# vakuum2.net
KiCad netlist of a schematic drawn in EAGLE
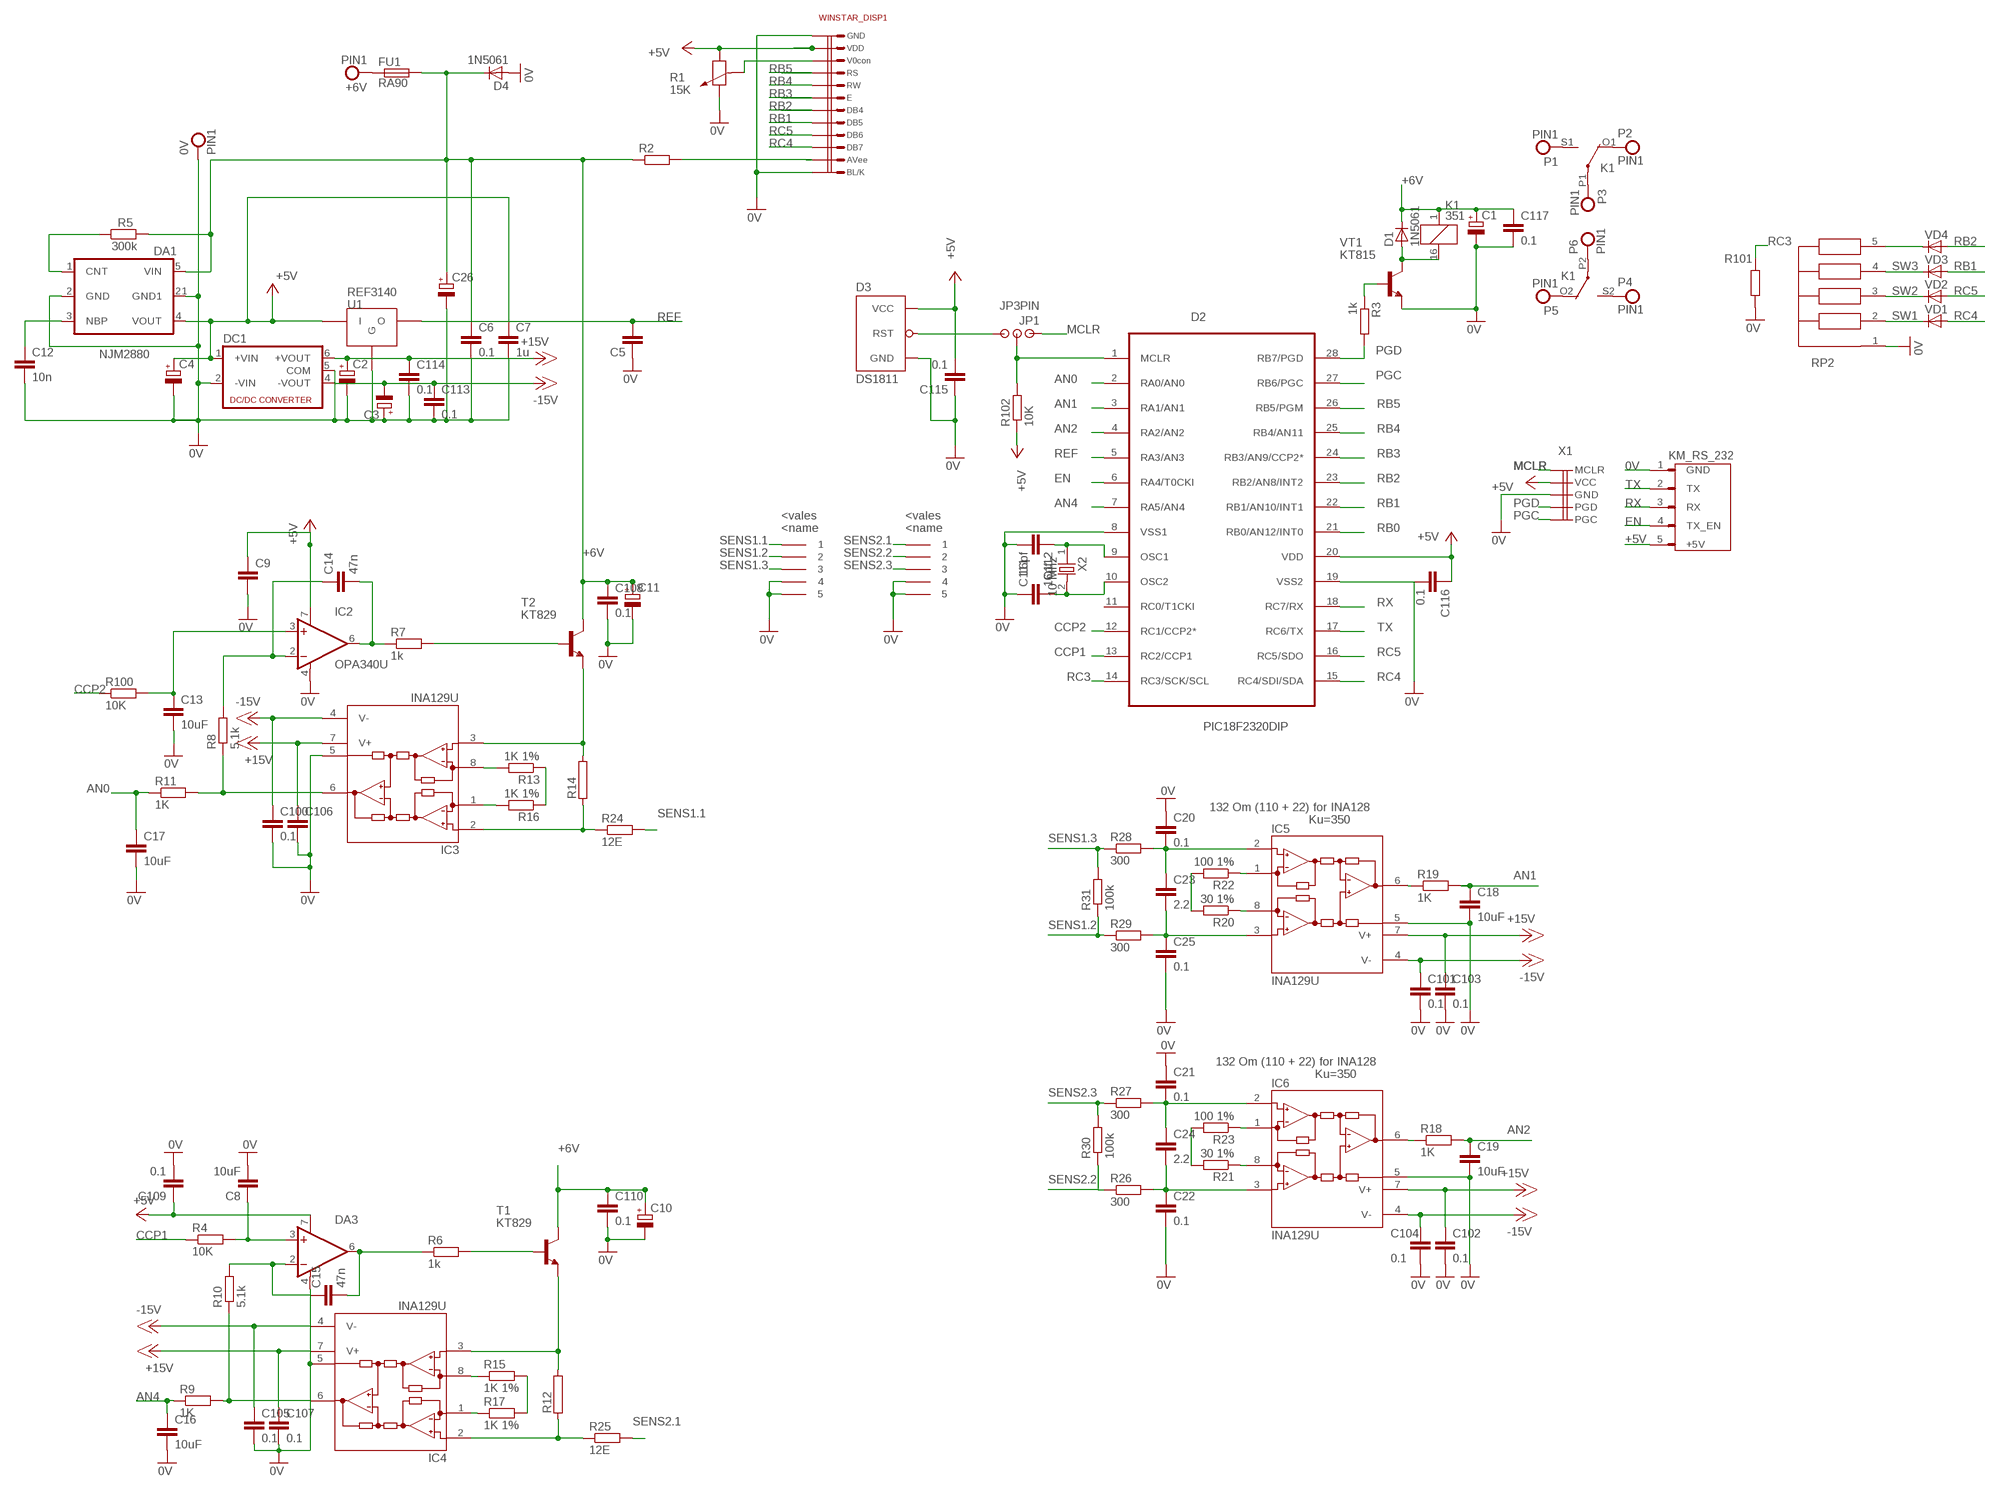
[diagram p0: schematic, sheet 1]

(export (version "E")
  (design (tool "Eeschema 10.0.6"))
  (components
    (comp (ref "+6V")
      (value "PIN1")
      (footprint "eagle-import:PIN1")
      (libsource (lib "eagle-import") (part "PIN1"))
    )
    (comp (ref "0V")
      (value "PIN1")
      (footprint "eagle-import:PIN1")
      (libsource (lib "eagle-import") (part "PIN1"))
    )
    (comp (ref "C1")
      (value "C100MFX25V")
      (footprint "eagle-import:C100MILX6X12")
      (libsource (lib "eagle-import") (part "C100MFX25V"))
    )
    (comp (ref "C2")
      (value "C100MFX25V")
      (footprint "eagle-import:C100MILX6X12")
      (libsource (lib "eagle-import") (part "C100MFX25V"))
    )
    (comp (ref "C3")
      (value "C100MFX25V")
      (footprint "eagle-import:C100MILX6X12")
      (libsource (lib "eagle-import") (part "C100MFX25V"))
    )
    (comp (ref "C4")
      (value "C100MFX25V")
      (footprint "eagle-import:C100MILX6X12")
      (libsource (lib "eagle-import") (part "C100MFX25V"))
    )
    (comp (ref "C5")
      (value "C0805")
      (footprint "eagle-import:C0805D")
      (libsource (lib "eagle-import") (part "C0805"))
    )
    (comp (ref "C6")
      (value "0.1")
      (footprint "eagle-import:C0805D")
      (libsource (lib "eagle-import") (part "C0805"))
    )
    (comp (ref "C7")
      (value "1u")
      (footprint "eagle-import:C0805D")
      (libsource (lib "eagle-import") (part "C0805"))
    )
    (comp (ref "C8")
      (value "10uF")
      (footprint "eagle-import:C0805D")
      (libsource (lib "eagle-import") (part "C0805"))
    )
    (comp (ref "C9")
      (value "C0805")
      (footprint "eagle-import:C0805D")
      (libsource (lib "eagle-import") (part "C0805"))
    )
    (comp (ref "C10")
      (value "C100MFX25V")
      (footprint "eagle-import:C100MILX6X12")
      (libsource (lib "eagle-import") (part "C100MFX25V"))
    )
    (comp (ref "C11")
      (value "C100MFX25V")
      (footprint "eagle-import:C100MILX6X12")
      (libsource (lib "eagle-import") (part "C100MFX25V"))
    )
    (comp (ref "C12")
      (value "10n")
      (footprint "eagle-import:C0805D")
      (libsource (lib "eagle-import") (part "C0805"))
    )
    (comp (ref "C13")
      (value "10uF")
      (footprint "eagle-import:C0805D")
      (libsource (lib "eagle-import") (part "C0805"))
    )
    (comp (ref "C14")
      (value "47n")
      (footprint "eagle-import:C0805D")
      (libsource (lib "eagle-import") (part "C0805"))
    )
    (comp (ref "C15")
      (value "47n")
      (footprint "eagle-import:C0805D")
      (libsource (lib "eagle-import") (part "C0805"))
    )
    (comp (ref "C16")
      (value "10uF")
      (footprint "eagle-import:C0805D")
      (libsource (lib "eagle-import") (part "C0805"))
    )
    (comp (ref "C17")
      (value "10uF")
      (footprint "eagle-import:C0805D")
      (libsource (lib "eagle-import") (part "C0805"))
    )
    (comp (ref "C18")
      (value "10uF")
      (footprint "eagle-import:C0805D")
      (libsource (lib "eagle-import") (part "C0805"))
    )
    (comp (ref "C19")
      (value "10uF")
      (footprint "eagle-import:C0805D")
      (libsource (lib "eagle-import") (part "C0805"))
    )
    (comp (ref "C20")
      (value "0.1")
      (footprint "eagle-import:C0805D")
      (libsource (lib "eagle-import") (part "C0805"))
    )
    (comp (ref "C21")
      (value "0.1")
      (footprint "eagle-import:C0805D")
      (libsource (lib "eagle-import") (part "C0805"))
    )
    (comp (ref "C22")
      (value "0.1")
      (footprint "eagle-import:C0805D")
      (libsource (lib "eagle-import") (part "C0805"))
    )
    (comp (ref "C23")
      (value "2.2")
      (footprint "eagle-import:C0805D")
      (libsource (lib "eagle-import") (part "C0805"))
    )
    (comp (ref "C24")
      (value "2.2")
      (footprint "eagle-import:C0805D")
      (libsource (lib "eagle-import") (part "C0805"))
    )
    (comp (ref "C25")
      (value "0.1")
      (footprint "eagle-import:C0805D")
      (libsource (lib "eagle-import") (part "C0805"))
    )
    (comp (ref "C26")
      (value "C100MFX25V")
      (footprint "eagle-import:C100MILX6X12")
      (libsource (lib "eagle-import") (part "C100MFX25V"))
    )
    (comp (ref "C100")
      (value "0.1")
      (footprint "eagle-import:C0805D")
      (libsource (lib "eagle-import") (part "C0805"))
    )
    (comp (ref "C101")
      (value "0.1")
      (footprint "eagle-import:C0805D")
      (libsource (lib "eagle-import") (part "C0805"))
    )
    (comp (ref "C102")
      (value "0.1")
      (footprint "eagle-import:C0805D")
      (libsource (lib "eagle-import") (part "C0805"))
    )
    (comp (ref "C103")
      (value "0.1")
      (footprint "eagle-import:C0805D")
      (libsource (lib "eagle-import") (part "C0805"))
    )
    (comp (ref "C104")
      (value "0.1")
      (footprint "eagle-import:C0805D")
      (libsource (lib "eagle-import") (part "C0805"))
    )
    (comp (ref "C105")
      (value "0.1")
      (footprint "eagle-import:C0805D")
      (libsource (lib "eagle-import") (part "C0805"))
    )
    (comp (ref "C106")
      (value "C0805")
      (footprint "eagle-import:C0805D")
      (libsource (lib "eagle-import") (part "C0805"))
    )
    (comp (ref "C107")
      (value "0.1")
      (footprint "eagle-import:C0805D")
      (libsource (lib "eagle-import") (part "C0805"))
    )
    (comp (ref "C108")
      (value "0.1")
      (footprint "eagle-import:C0805D")
      (libsource (lib "eagle-import") (part "C0805"))
    )
    (comp (ref "C109")
      (value "0.1")
      (footprint "eagle-import:C0805D")
      (libsource (lib "eagle-import") (part "C0805"))
    )
    (comp (ref "C110")
      (value "0.1")
      (footprint "eagle-import:C0805D")
      (libsource (lib "eagle-import") (part "C0805"))
    )
    (comp (ref "C111")
      (value "16pf")
      (footprint "eagle-import:C0805D")
      (libsource (lib "eagle-import") (part "C0805"))
    )
    (comp (ref "C112")
      (value "16pf")
      (footprint "eagle-import:C0805D")
      (libsource (lib "eagle-import") (part "C0805"))
    )
    (comp (ref "C113")
      (value "0.1")
      (footprint "eagle-import:C0805D")
      (libsource (lib "eagle-import") (part "C0805"))
    )
    (comp (ref "C114")
      (value "0.1")
      (footprint "eagle-import:C0805D")
      (libsource (lib "eagle-import") (part "C0805"))
    )
    (comp (ref "C115")
      (value "0.1")
      (footprint "eagle-import:C0805D")
      (libsource (lib "eagle-import") (part "C0805"))
    )
    (comp (ref "C116")
      (value "0.1")
      (footprint "eagle-import:C0805D")
      (libsource (lib "eagle-import") (part "C0805"))
    )
    (comp (ref "C117")
      (value "0.1")
      (footprint "eagle-import:C0805D")
      (libsource (lib "eagle-import") (part "C0805"))
    )
    (comp (ref "D1")
      (value "1N5061")
      (footprint "eagle-import:DO41-10")
      (libsource (lib "eagle-import") (part "1N5061"))
    )
    (comp (ref "D2")
      (value "PIC18F2320DIP")
      (footprint "eagle-import:DIL28-3")
      (libsource (lib "eagle-import") (part "PIC18F2320DIP"))
    )
    (comp (ref "D3")
      (value "DS1811")
      (footprint "eagle-import:TO92-60")
      (libsource (lib "eagle-import") (part "DS1811"))
    )
    (comp (ref "D4")
      (value "1N5061")
      (footprint "eagle-import:DO41-10")
      (libsource (lib "eagle-import") (part "1N5061"))
    )
    (comp (ref "DA1")
      (value "NJM2880")
      (footprint "eagle-import:SOT89-5")
      (libsource (lib "eagle-import") (part "NJM2880"))
    )
    (comp (ref "DA3")
      (value "OPA340U")
      (footprint "eagle-import:SO08")
      (fields (field (name "MPN") "OPA340UA"))
      (libsource (lib "eagle-import") (part "OPA340U"))
    )
    (comp (ref "DC1")
      (value "NMA")
      (footprint "eagle-import:NMA")
      (fields (field (name "MF") "C & D TECHNOLOGIES, INC") (field (name "MPN") "NMA0515SC"))
      (libsource (lib "eagle-import") (part "NMA"))
    )
    (comp (ref "FU1")
      (value "RA90")
      (footprint "eagle-import:RA90")
      (libsource (lib "eagle-import") (part "RA90"))
    )
    (comp (ref "IC2")
      (value "OPA340U")
      (footprint "eagle-import:SO08")
      (fields (field (name "MPN") "OPA340UA"))
      (libsource (lib "eagle-import") (part "OPA340U"))
    )
    (comp (ref "IC3")
      (value "INA129U")
      (footprint "eagle-import:SO08")
      (fields (field (name "MF") "TEXAS INSTRUMENTS"))
      (libsource (lib "eagle-import") (part "INA129U"))
    )
    (comp (ref "IC4")
      (value "INA129U")
      (footprint "eagle-import:SO08")
      (fields (field (name "MF") "TEXAS INSTRUMENTS"))
      (libsource (lib "eagle-import") (part "INA129U"))
    )
    (comp (ref "IC5")
      (value "INA129U")
      (footprint "eagle-import:SO08")
      (fields (field (name "MF") "TEXAS INSTRUMENTS"))
      (libsource (lib "eagle-import") (part "INA129U"))
    )
    (comp (ref "IC6")
      (value "INA129U")
      (footprint "eagle-import:SO08")
      (fields (field (name "MF") "TEXAS INSTRUMENTS"))
      (libsource (lib "eagle-import") (part "INA129U"))
    )
    (comp (ref "JP1")
      (value "JP3PIN")
      (footprint "eagle-import:PLC-3PIN")
      (libsource (lib "eagle-import") (part "JP3PIN"))
    )
    (comp (ref "K1")
      (value "351")
      (footprint "eagle-import:351")
      (libsource (lib "eagle-import") (part "351"))
    )
    (comp (ref "P1")
      (value "PIN1")
      (footprint "eagle-import:PIN1")
      (libsource (lib "eagle-import") (part "PIN1"))
    )
    (comp (ref "P2")
      (value "PIN1")
      (footprint "eagle-import:PIN1")
      (libsource (lib "eagle-import") (part "PIN1"))
    )
    (comp (ref "P3")
      (value "PIN1")
      (footprint "eagle-import:PIN1")
      (libsource (lib "eagle-import") (part "PIN1"))
    )
    (comp (ref "P4")
      (value "PIN1")
      (footprint "eagle-import:PIN1")
      (libsource (lib "eagle-import") (part "PIN1"))
    )
    (comp (ref "P5")
      (value "PIN1")
      (footprint "eagle-import:PIN1")
      (libsource (lib "eagle-import") (part "PIN1"))
    )
    (comp (ref "P6")
      (value "PIN1")
      (footprint "eagle-import:PIN1")
      (libsource (lib "eagle-import") (part "PIN1"))
    )
    (comp (ref "R1")
      (value "15K")
      (footprint "eagle-import:RTRIM3329H")
      (libsource (lib "eagle-import") (part "RTRIM3329H"))
    )
    (comp (ref "R2")
      (value "MLT025\"")
      (footprint "eagle-import:0207_10")
      (libsource (lib "eagle-import") (part "MLT025{dblquote}"))
    )
    (comp (ref "R3")
      (value "1k")
      (footprint "eagle-import:0207_10")
      (libsource (lib "eagle-import") (part "MLT025{dblquote}"))
    )
    (comp (ref "R4")
      (value "10K")
      (footprint "eagle-import:R0805D")
      (libsource (lib "eagle-import") (part "R0805"))
    )
    (comp (ref "R5")
      (value "300k")
      (footprint "eagle-import:R0805D")
      (libsource (lib "eagle-import") (part "R0805"))
    )
    (comp (ref "R6")
      (value "1k")
      (footprint "eagle-import:0207_10")
      (libsource (lib "eagle-import") (part "MLT025{dblquote}"))
    )
    (comp (ref "R7")
      (value "1k")
      (footprint "eagle-import:R0805D")
      (libsource (lib "eagle-import") (part "R0805"))
    )
    (comp (ref "R8")
      (value "5.1k")
      (footprint "eagle-import:R0805D")
      (libsource (lib "eagle-import") (part "R0805"))
    )
    (comp (ref "R9")
      (value "1K")
      (footprint "eagle-import:R0805D")
      (libsource (lib "eagle-import") (part "R0805"))
    )
    (comp (ref "R10")
      (value "5.1k")
      (footprint "eagle-import:R0805D")
      (libsource (lib "eagle-import") (part "R0805"))
    )
    (comp (ref "R11")
      (value "1K")
      (footprint "eagle-import:R0805D")
      (libsource (lib "eagle-import") (part "R0805"))
    )
    (comp (ref "R12")
      (value "RHPS932")
      (footprint "eagle-import:HPS932")
      (libsource (lib "eagle-import") (part "RHPS932"))
    )
    (comp (ref "R13")
      (value "1K 1%")
      (footprint "eagle-import:R0805D")
      (libsource (lib "eagle-import") (part "R0805"))
    )
    (comp (ref "R14")
      (value "RHPS932")
      (footprint "eagle-import:HPS932")
      (libsource (lib "eagle-import") (part "RHPS932"))
    )
    (comp (ref "R15")
      (value "1K 1%")
      (footprint "eagle-import:R0805D")
      (libsource (lib "eagle-import") (part "R0805"))
    )
    (comp (ref "R16")
      (value "1K 1%")
      (footprint "eagle-import:R0805D")
      (libsource (lib "eagle-import") (part "R0805"))
    )
    (comp (ref "R17")
      (value "1K 1%")
      (footprint "eagle-import:R0805D")
      (libsource (lib "eagle-import") (part "R0805"))
    )
    (comp (ref "R18")
      (value "1K")
      (footprint "eagle-import:R0805D")
      (libsource (lib "eagle-import") (part "R0805"))
    )
    (comp (ref "R19")
      (value "1K")
      (footprint "eagle-import:R0805D")
      (libsource (lib "eagle-import") (part "R0805"))
    )
    (comp (ref "R20")
      (value "30 1%")
      (footprint "eagle-import:R0805D")
      (libsource (lib "eagle-import") (part "R0805"))
    )
    (comp (ref "R21")
      (value "30 1%")
      (footprint "eagle-import:R0805D")
      (libsource (lib "eagle-import") (part "R0805"))
    )
    (comp (ref "R22")
      (value "100 1%")
      (footprint "eagle-import:R0805D")
      (libsource (lib "eagle-import") (part "R0805"))
    )
    (comp (ref "R23")
      (value "100 1%")
      (footprint "eagle-import:R0805D")
      (libsource (lib "eagle-import") (part "R0805"))
    )
    (comp (ref "R24")
      (value "12E")
      (footprint "eagle-import:0207_10")
      (libsource (lib "eagle-import") (part "MLT025{dblquote}"))
    )
    (comp (ref "R25")
      (value "12E")
      (footprint "eagle-import:0207_10")
      (libsource (lib "eagle-import") (part "MLT025{dblquote}"))
    )
    (comp (ref "R26")
      (value "300")
      (footprint "eagle-import:R0805D")
      (libsource (lib "eagle-import") (part "R0805"))
    )
    (comp (ref "R27")
      (value "300")
      (footprint "eagle-import:R0805D")
      (libsource (lib "eagle-import") (part "R0805"))
    )
    (comp (ref "R28")
      (value "300")
      (footprint "eagle-import:R0805D")
      (libsource (lib "eagle-import") (part "R0805"))
    )
    (comp (ref "R29")
      (value "300")
      (footprint "eagle-import:R0805D")
      (libsource (lib "eagle-import") (part "R0805"))
    )
    (comp (ref "R30")
      (value "100k")
      (footprint "eagle-import:R0805D")
      (libsource (lib "eagle-import") (part "R0805"))
    )
    (comp (ref "R31")
      (value "100k")
      (footprint "eagle-import:R0805D")
      (libsource (lib "eagle-import") (part "R0805"))
    )
    (comp (ref "R100")
      (value "10K")
      (footprint "eagle-import:R0805D")
      (libsource (lib "eagle-import") (part "R0805"))
    )
    (comp (ref "R101")
      (value "10k")
      (footprint "eagle-import:R0805D")
      (libsource (lib "eagle-import") (part "R0805"))
    )
    (comp (ref "R102")
      (value "10K")
      (footprint "eagle-import:R0805D")
      (libsource (lib "eagle-import") (part "R0805"))
    )
    (comp (ref "RP2")
      (value "NR1-4-4")
      (footprint "eagle-import:SIP5")
      (libsource (lib "eagle-import") (part "NR1-4-4"))
    )
    (comp (ref "T1")
      (value "KT829")
      (footprint "eagle-import:T-30")
      (libsource (lib "eagle-import") (part "2SC1969H"))
    )
    (comp (ref "T2")
      (value "KT829")
      (footprint "eagle-import:T-30")
      (libsource (lib "eagle-import") (part "2SC1969H"))
    )
    (comp (ref "U1")
      (value "REF3140")
      (footprint "eagle-import:SOT23-W")
      (libsource (lib "eagle-import") (part "REF3140"))
    )
    (comp (ref "VD1")
      (value "KD521")
      (footprint "eagle-import:DO35-10")
      (libsource (lib "eagle-import") (part "KD521"))
    )
    (comp (ref "VD2")
      (value "KD521")
      (footprint "eagle-import:DO35-10")
      (libsource (lib "eagle-import") (part "KD521"))
    )
    (comp (ref "VD3")
      (value "KD521")
      (footprint "eagle-import:DO35-10")
      (libsource (lib "eagle-import") (part "KD521"))
    )
    (comp (ref "VD4")
      (value "KD521")
      (footprint "eagle-import:DO35-10")
      (libsource (lib "eagle-import") (part "KD521"))
    )
    (comp (ref "VT1")
      (value "KT815")
      (footprint "eagle-import:TO126V")
      (libsource (lib "eagle-import") (part "KT815"))
    )
    (comp (ref "WINSTAR_DISP1")
      (value "WINSTAR16X4DSPL_12")
      (footprint "eagle-import:WINSTAR16X4_12")
      (libsource (lib "eagle-import") (part "WINSTAR16X4DSPL_12"))
    )
    (comp (ref "X1")
      (value "PIC_ISP_CONN")
      (footprint "eagle-import:PLC-5PIN")
      (libsource (lib "eagle-import") (part "PIC_ISP_CONN"))
    )
    (comp (ref "X2")
      (value "10 Mhz")
      (footprint "eagle-import:HC49_S")
      (libsource (lib "eagle-import") (part "HC49/S"))
    )
    (comp (ref "X3")
      (value "KM_RS_232")
      (footprint "eagle-import:KM_RS_232")
      (libsource (lib "eagle-import") (part "KM_RS_232"))
    )
    (comp (ref "X4")
      (value "MB332-381")
      (footprint "eagle-import:MB332-381")
      (libsource (lib "eagle-import") (part "MB332-381"))
    )
    (comp (ref "X5")
      (value "MB332-381")
      (footprint "eagle-import:MB332-381")
      (libsource (lib "eagle-import") (part "MB332-381"))
    )
  )
  (nets
    (net (code "1") (name "+5V") (class "Default")
      (node (ref "C109") (pin "1") (pinfunction "1_1") (pintype "passive"))
      (node (ref "C115") (pin "2") (pinfunction "2_2") (pintype "passive"))
      (node (ref "C116") (pin "1") (pinfunction "1_1") (pintype "passive"))
      (node (ref "C4") (pin "PLUS") (pinfunction "+_PLUS") (pintype "passive"))
      (node (ref "C7") (pin "1") (pinfunction "1_1") (pintype "passive"))
      (node (ref "C9") (pin "1") (pinfunction "1_1") (pintype "passive"))
      (node (ref "D2") (pin "20") (pinfunction "VDD_20") (pintype "bidirectional"))
      (node (ref "D3") (pin "2") (pinfunction "VCC_2") (pintype "power_in"))
      (node (ref "DA1") (pin "4") (pinfunction "VOUT_4") (pintype "bidirectional"))
      (node (ref "DA3") (pin "7") (pinfunction "V+_7") (pintype "power_in"))
      (node (ref "DC1") (pin "1") (pinfunction "+VIN_1") (pintype "passive"))
      (node (ref "IC2") (pin "7") (pinfunction "V+_7") (pintype "power_in"))
      (node (ref "R1") (pin "1") (pinfunction "1_1") (pintype "passive"))
      (node (ref "R102") (pin "P$1") (pinfunction "1_P$1") (pintype "passive"))
      (node (ref "U1") (pin "IN") (pinfunction "I_IN") (pintype "bidirectional"))
      (node (ref "WINSTAR_DISP1") (pin "P$2") (pinfunction "VDD_P$2") (pintype "bidirectional"))
      (node (ref "X1") (pin "P$2") (pinfunction "VCC_P$2") (pintype "bidirectional"))
      (node (ref "X3") (pin "5") (pinfunction "+5V_5") (pintype "bidirectional"))
    )
    (net (code "2") (name "+15V") (class "Default")
      (node (ref "C102") (pin "1") (pinfunction "1_1") (pintype "passive"))
      (node (ref "C103") (pin "1") (pinfunction "1_1") (pintype "passive"))
      (node (ref "C106") (pin "1") (pinfunction "1_1") (pintype "passive"))
      (node (ref "C107") (pin "1") (pinfunction "1_1") (pintype "passive"))
      (node (ref "C114") (pin "1") (pinfunction "1_1") (pintype "passive"))
      (node (ref "C2") (pin "PLUS") (pinfunction "+_PLUS") (pintype "passive"))
      (node (ref "DC1") (pin "6") (pinfunction "+VOUT_6") (pintype "passive"))
      (node (ref "IC3") (pin "7") (pinfunction "V+_7") (pintype "power_in"))
      (node (ref "IC4") (pin "7") (pinfunction "V+_7") (pintype "power_in"))
      (node (ref "IC5") (pin "7") (pinfunction "V+_7") (pintype "power_in"))
      (node (ref "IC6") (pin "7") (pinfunction "V+_7") (pintype "power_in"))
    )
    (net (code "3") (name "-15V") (class "Default")
      (node (ref "C100") (pin "1") (pinfunction "1_1") (pintype "passive"))
      (node (ref "C101") (pin "1") (pinfunction "1_1") (pintype "passive"))
      (node (ref "C104") (pin "1") (pinfunction "1_1") (pintype "passive"))
      (node (ref "C105") (pin "1") (pinfunction "1_1") (pintype "passive"))
      (node (ref "C113") (pin "1") (pinfunction "1_1") (pintype "passive"))
      (node (ref "C3") (pin "MINUS") (pinfunction "-_MINUS") (pintype "passive"))
      (node (ref "DC1") (pin "4") (pinfunction "-VOUT_4") (pintype "passive"))
      (node (ref "IC3") (pin "4") (pinfunction "V-_4") (pintype "power_in"))
      (node (ref "IC4") (pin "4") (pinfunction "V-_4") (pintype "power_in"))
      (node (ref "IC5") (pin "4") (pinfunction "V-_4") (pintype "power_in"))
      (node (ref "IC6") (pin "4") (pinfunction "V-_4") (pintype "power_in"))
    )
    (net (code "4") (name "/+6V") (class "Default")
      (node (ref "C1") (pin "PLUS") (pinfunction "+_PLUS") (pintype "passive"))
      (node (ref "C10") (pin "PLUS") (pinfunction "+_PLUS") (pintype "passive"))
      (node (ref "C108") (pin "1") (pinfunction "1_1") (pintype "passive"))
      (node (ref "C11") (pin "PLUS") (pinfunction "+_PLUS") (pintype "passive"))
      (node (ref "C110") (pin "1") (pinfunction "1_1") (pintype "passive"))
      (node (ref "C117") (pin "1") (pinfunction "1_1") (pintype "passive"))
      (node (ref "C26") (pin "PLUS") (pinfunction "+_PLUS") (pintype "passive"))
      (node (ref "C6") (pin "1") (pinfunction "1_1") (pintype "passive"))
      (node (ref "D1") (pin "C") (pinfunction "C_C") (pintype "passive"))
      (node (ref "D4") (pin "C") (pinfunction "C_C") (pintype "passive"))
      (node (ref "DA1") (pin "5") (pinfunction "VIN_5") (pintype "bidirectional"))
      (node (ref "FU1") (pin "P$2") (pinfunction "2_P$2") (pintype "passive"))
      (node (ref "K1") (pin "1") (pinfunction "1_1") (pintype "passive"))
      (node (ref "R2") (pin "1") (pinfunction "1_1") (pintype "passive"))
      (node (ref "R5") (pin "P$2") (pinfunction "2_P$2") (pintype "passive"))
      (node (ref "T1") (pin "2") (pinfunction "C_2") (pintype "passive"))
      (node (ref "T2") (pin "2") (pinfunction "C_2") (pintype "passive"))
    )
    (net (code "5") (name "/AN0") (class "Default")
      (node (ref "C17") (pin "1") (pinfunction "1_1") (pintype "passive"))
      (node (ref "D2") (pin "2") (pinfunction "RA0/AN0_2") (pintype "bidirectional"))
      (node (ref "R11") (pin "P$1") (pinfunction "1_P$1") (pintype "passive"))
    )
    (net (code "6") (name "/AN1") (class "Default")
      (node (ref "C18") (pin "1") (pinfunction "1_1") (pintype "passive"))
      (node (ref "D2") (pin "3") (pinfunction "RA1/AN1_3") (pintype "bidirectional"))
      (node (ref "R19") (pin "P$2") (pinfunction "2_P$2") (pintype "passive"))
    )
    (net (code "7") (name "/AN2") (class "Default")
      (node (ref "C19") (pin "1") (pinfunction "1_1") (pintype "passive"))
      (node (ref "D2") (pin "4") (pinfunction "RA2/AN2_4") (pintype "bidirectional"))
      (node (ref "R18") (pin "P$2") (pinfunction "2_P$2") (pintype "passive"))
    )
    (net (code "8") (name "/AN4") (class "Default")
      (node (ref "C16") (pin "1") (pinfunction "1_1") (pintype "passive"))
      (node (ref "D2") (pin "7") (pinfunction "RA5/AN4_7") (pintype "bidirectional"))
      (node (ref "R9") (pin "P$1") (pinfunction "1_P$1") (pintype "passive"))
    )
    (net (code "9") (name "/CCP1") (class "Default")
      (node (ref "D2") (pin "13") (pinfunction "RC2/CCP1_13") (pintype "bidirectional"))
      (node (ref "R4") (pin "P$1") (pinfunction "1_P$1") (pintype "passive"))
    )
    (net (code "10") (name "/CCP2") (class "Default")
      (node (ref "D2") (pin "12") (pinfunction "RC1/CCP2*_12") (pintype "bidirectional"))
      (node (ref "R100") (pin "P$1") (pinfunction "1_P$1") (pintype "passive"))
    )
    (net (code "11") (name "/EN") (class "Default")
      (node (ref "D2") (pin "6") (pinfunction "RA4/T0CKI_6") (pintype "bidirectional"))
      (node (ref "X3") (pin "4") (pinfunction "TX_EN_4") (pintype "bidirectional"))
    )
    (net (code "12") (name "/MCLR") (class "Default")
      (node (ref "JP1") (pin "P$1") (pinfunction "P$1_P$1") (pintype "bidirectional"))
      (node (ref "X1") (pin "P$1") (pinfunction "MCLR_P$1") (pintype "bidirectional"))
    )
    (net (code "13") (name "/PGC") (class "Default")
      (node (ref "D2") (pin "27") (pinfunction "RB6/PGC_27") (pintype "bidirectional"))
      (node (ref "X1") (pin "P$5") (pinfunction "PGC_P$5") (pintype "bidirectional"))
    )
    (net (code "14") (name "/PGD") (class "Default")
      (node (ref "D2") (pin "28") (pinfunction "RB7/PGD_28") (pintype "bidirectional"))
      (node (ref "R3") (pin "2") (pinfunction "2_2") (pintype "passive"))
      (node (ref "X1") (pin "P$4") (pinfunction "PGD_P$4") (pintype "bidirectional"))
    )
    (net (code "15") (name "/RB0") (class "Default")
      (node (ref "D2") (pin "21") (pinfunction "RB0/AN12/INT0_21") (pintype "bidirectional"))
    )
    (net (code "16") (name "/RB1") (class "Default")
      (node (ref "D2") (pin "22") (pinfunction "RB1/AN10/INT1_22") (pintype "bidirectional"))
      (node (ref "VD3") (pin "A") (pinfunction "A_A") (pintype "passive"))
      (node (ref "WINSTAR_DISP1") (pin "P$8") (pinfunction "DB5_P$8") (pintype "bidirectional"))
    )
    (net (code "17") (name "/RB2") (class "Default")
      (node (ref "D2") (pin "23") (pinfunction "RB2/AN8/INT2_23") (pintype "bidirectional"))
      (node (ref "VD4") (pin "A") (pinfunction "A_A") (pintype "passive"))
      (node (ref "WINSTAR_DISP1") (pin "P$7") (pinfunction "DB4_P$7") (pintype "bidirectional"))
    )
    (net (code "18") (name "/RB3") (class "Default")
      (node (ref "D2") (pin "24") (pinfunction "RB3/AN9/CCP2*_24") (pintype "bidirectional"))
      (node (ref "WINSTAR_DISP1") (pin "P$6") (pinfunction "E_P$6") (pintype "bidirectional"))
    )
    (net (code "19") (name "/RB4") (class "Default")
      (node (ref "D2") (pin "25") (pinfunction "RB4/AN11_25") (pintype "bidirectional"))
      (node (ref "WINSTAR_DISP1") (pin "P$5") (pinfunction "RW_P$5") (pintype "bidirectional"))
    )
    (net (code "20") (name "/RB5") (class "Default")
      (node (ref "D2") (pin "26") (pinfunction "RB5/PGM_26") (pintype "bidirectional"))
      (node (ref "WINSTAR_DISP1") (pin "P$4") (pinfunction "RS_P$4") (pintype "bidirectional"))
    )
    (net (code "21") (name "/RC3") (class "Default")
      (node (ref "D2") (pin "14") (pinfunction "RC3/SCK/SCL_14") (pintype "bidirectional"))
      (node (ref "R101") (pin "P$1") (pinfunction "1_P$1") (pintype "passive"))
    )
    (net (code "22") (name "/RC4") (class "Default")
      (node (ref "D2") (pin "15") (pinfunction "RC4/SDI/SDA_15") (pintype "bidirectional"))
      (node (ref "VD1") (pin "A") (pinfunction "A_A") (pintype "passive"))
      (node (ref "WINSTAR_DISP1") (pin "P$10") (pinfunction "DB7_P$10") (pintype "bidirectional"))
    )
    (net (code "23") (name "/RC5") (class "Default")
      (node (ref "D2") (pin "16") (pinfunction "RC5/SDO_16") (pintype "bidirectional"))
      (node (ref "VD2") (pin "A") (pinfunction "A_A") (pintype "passive"))
      (node (ref "WINSTAR_DISP1") (pin "P$9") (pinfunction "DB6_P$9") (pintype "bidirectional"))
    )
    (net (code "24") (name "/REF") (class "Default")
      (node (ref "C5") (pin "2") (pinfunction "2_2") (pintype "passive"))
      (node (ref "D2") (pin "5") (pinfunction "RA3/AN3_5") (pintype "bidirectional"))
      (node (ref "U1") (pin "OUT") (pinfunction "O_OUT") (pintype "bidirectional"))
    )
    (net (code "25") (name "/RX") (class "Default")
      (node (ref "D2") (pin "18") (pinfunction "RC7/RX_18") (pintype "bidirectional"))
      (node (ref "X3") (pin "3") (pinfunction "RX_3") (pintype "bidirectional"))
    )
    (net (code "26") (name "/SENS1.1") (class "Default")
      (node (ref "R24") (pin "2") (pinfunction "2_2") (pintype "passive"))
      (node (ref "X4") (pin "1") (pinfunction "1_1") (pintype "bidirectional"))
    )
    (net (code "27") (name "/SENS1.2") (class "Default")
      (node (ref "R29") (pin "P$1") (pinfunction "1_P$1") (pintype "passive"))
      (node (ref "R31") (pin "P$1") (pinfunction "1_P$1") (pintype "passive"))
      (node (ref "X4") (pin "2") (pinfunction "2_2") (pintype "bidirectional"))
    )
    (net (code "28") (name "/SENS1.3") (class "Default")
      (node (ref "R28") (pin "P$1") (pinfunction "1_P$1") (pintype "passive"))
      (node (ref "R31") (pin "P$2") (pinfunction "2_P$2") (pintype "passive"))
      (node (ref "X4") (pin "3") (pinfunction "3_3") (pintype "bidirectional"))
    )
    (net (code "29") (name "/SENS2.1") (class "Default")
      (node (ref "R25") (pin "2") (pinfunction "2_2") (pintype "passive"))
      (node (ref "X5") (pin "1") (pinfunction "1_1") (pintype "bidirectional"))
    )
    (net (code "30") (name "/SENS2.2") (class "Default")
      (node (ref "R26") (pin "P$1") (pinfunction "1_P$1") (pintype "passive"))
      (node (ref "R30") (pin "P$1") (pinfunction "1_P$1") (pintype "passive"))
      (node (ref "X5") (pin "2") (pinfunction "2_2") (pintype "bidirectional"))
    )
    (net (code "31") (name "/SENS2.3") (class "Default")
      (node (ref "R27") (pin "P$1") (pinfunction "1_P$1") (pintype "passive"))
      (node (ref "R30") (pin "P$2") (pinfunction "2_P$2") (pintype "passive"))
      (node (ref "X5") (pin "3") (pinfunction "3_3") (pintype "bidirectional"))
    )
    (net (code "32") (name "/SW1") (class "Default")
      (node (ref "RP2") (pin "2") (pinfunction "P$2_2") (pintype "passive"))
      (node (ref "VD1") (pin "C") (pinfunction "C_C") (pintype "passive"))
    )
    (net (code "33") (name "/SW2") (class "Default")
      (node (ref "RP2") (pin "3") (pinfunction "P$3_3") (pintype "passive"))
      (node (ref "VD2") (pin "C") (pinfunction "C_C") (pintype "passive"))
    )
    (net (code "34") (name "/SW3") (class "Default")
      (node (ref "RP2") (pin "4") (pinfunction "P$4_4") (pintype "passive"))
      (node (ref "VD3") (pin "C") (pinfunction "C_C") (pintype "passive"))
    )
    (net (code "35") (name "/TX") (class "Default")
      (node (ref "D2") (pin "17") (pinfunction "RC6/TX_17") (pintype "bidirectional"))
      (node (ref "X3") (pin "2") (pinfunction "TX_2") (pintype "bidirectional"))
    )
    (net (code "36") (name "0V") (class "Default")
      (node (ref "0V") (pin "P$1") (pinfunction "P$1_P$1") (pintype "passive"))
      (node (ref "C1") (pin "MINUS") (pinfunction "-_MINUS") (pintype "passive"))
      (node (ref "C10") (pin "MINUS") (pinfunction "-_MINUS") (pintype "passive"))
      (node (ref "C100") (pin "2") (pinfunction "2_2") (pintype "passive"))
      (node (ref "C101") (pin "2") (pinfunction "2_2") (pintype "passive"))
      (node (ref "C102") (pin "2") (pinfunction "2_2") (pintype "passive"))
      (node (ref "C103") (pin "2") (pinfunction "2_2") (pintype "passive"))
      (node (ref "C104") (pin "2") (pinfunction "2_2") (pintype "passive"))
      (node (ref "C105") (pin "2") (pinfunction "2_2") (pintype "passive"))
      (node (ref "C106") (pin "2") (pinfunction "2_2") (pintype "passive"))
      (node (ref "C107") (pin "2") (pinfunction "2_2") (pintype "passive"))
      (node (ref "C108") (pin "2") (pinfunction "2_2") (pintype "passive"))
      (node (ref "C109") (pin "2") (pinfunction "2_2") (pintype "passive"))
      (node (ref "C11") (pin "MINUS") (pinfunction "-_MINUS") (pintype "passive"))
      (node (ref "C110") (pin "2") (pinfunction "2_2") (pintype "passive"))
      (node (ref "C111") (pin "1") (pinfunction "1_1") (pintype "passive"))
      (node (ref "C112") (pin "2") (pinfunction "2_2") (pintype "passive"))
      (node (ref "C113") (pin "2") (pinfunction "2_2") (pintype "passive"))
      (node (ref "C114") (pin "2") (pinfunction "2_2") (pintype "passive"))
      (node (ref "C115") (pin "1") (pinfunction "1_1") (pintype "passive"))
      (node (ref "C116") (pin "2") (pinfunction "2_2") (pintype "passive"))
      (node (ref "C117") (pin "2") (pinfunction "2_2") (pintype "passive"))
      (node (ref "C12") (pin "2") (pinfunction "2_2") (pintype "passive"))
      (node (ref "C13") (pin "2") (pinfunction "2_2") (pintype "passive"))
      (node (ref "C16") (pin "2") (pinfunction "2_2") (pintype "passive"))
      (node (ref "C17") (pin "2") (pinfunction "2_2") (pintype "passive"))
      (node (ref "C18") (pin "2") (pinfunction "2_2") (pintype "passive"))
      (node (ref "C19") (pin "2") (pinfunction "2_2") (pintype "passive"))
      (node (ref "C2") (pin "MINUS") (pinfunction "-_MINUS") (pintype "passive"))
      (node (ref "C20") (pin "1") (pinfunction "1_1") (pintype "passive"))
      (node (ref "C21") (pin "1") (pinfunction "1_1") (pintype "passive"))
      (node (ref "C22") (pin "2") (pinfunction "2_2") (pintype "passive"))
      (node (ref "C25") (pin "2") (pinfunction "2_2") (pintype "passive"))
      (node (ref "C26") (pin "MINUS") (pinfunction "-_MINUS") (pintype "passive"))
      (node (ref "C3") (pin "PLUS") (pinfunction "+_PLUS") (pintype "passive"))
      (node (ref "C4") (pin "MINUS") (pinfunction "-_MINUS") (pintype "passive"))
      (node (ref "C5") (pin "1") (pinfunction "1_1") (pintype "passive"))
      (node (ref "C6") (pin "2") (pinfunction "2_2") (pintype "passive"))
      (node (ref "C7") (pin "2") (pinfunction "2_2") (pintype "passive"))
      (node (ref "C8") (pin "2") (pinfunction "2_2") (pintype "passive"))
      (node (ref "C9") (pin "2") (pinfunction "2_2") (pintype "passive"))
      (node (ref "D2") (pin "19") (pinfunction "VSS2_19") (pintype "bidirectional"))
      (node (ref "D2") (pin "8") (pinfunction "VSS1_8") (pintype "bidirectional"))
      (node (ref "D3") (pin "3") (pinfunction "GND_3") (pintype "power_in"))
      (node (ref "D4") (pin "A") (pinfunction "A_A") (pintype "passive"))
      (node (ref "DA1") (pin "2") (pinfunction "GND_2") (pintype "bidirectional"))
      (node (ref "DA1") (pin "21") (pinfunction "GND1_21") (pintype "bidirectional"))
      (node (ref "DA3") (pin "4") (pinfunction "V-_4") (pintype "power_in"))
      (node (ref "DC1") (pin "2") (pinfunction "-VIN_2") (pintype "passive"))
      (node (ref "DC1") (pin "5") (pinfunction "COM_5") (pintype "passive"))
      (node (ref "IC2") (pin "4") (pinfunction "V-_4") (pintype "power_in"))
      (node (ref "IC3") (pin "5") (pinfunction "REF_5") (pintype "passive"))
      (node (ref "IC4") (pin "5") (pinfunction "REF_5") (pintype "passive"))
      (node (ref "IC5") (pin "5") (pinfunction "REF_5") (pintype "passive"))
      (node (ref "IC6") (pin "5") (pinfunction "REF_5") (pintype "passive"))
      (node (ref "R1") (pin "2") (pinfunction "2_2") (pintype "passive"))
      (node (ref "R101") (pin "P$2") (pinfunction "2_P$2") (pintype "passive"))
      (node (ref "RP2") (pin "1") (pinfunction "P$1_1") (pintype "passive"))
      (node (ref "U1") (pin "GND") (pinfunction "G_GND") (pintype "bidirectional"))
      (node (ref "VT1") (pin "1") (pinfunction "E_1") (pintype "passive"))
      (node (ref "WINSTAR_DISP1") (pin "P$1") (pinfunction "GND_P$1") (pintype "bidirectional"))
      (node (ref "WINSTAR_DISP1") (pin "P$12") (pinfunction "KB/L_P$12") (pintype "bidirectional"))
      (node (ref "X1") (pin "P$3") (pinfunction "GND_P$3") (pintype "bidirectional"))
      (node (ref "X3") (pin "1") (pinfunction "GND_1") (pintype "bidirectional"))
      (node (ref "X4") (pin "4") (pinfunction "4_4") (pintype "bidirectional"))
      (node (ref "X4") (pin "5") (pinfunction "5_5") (pintype "bidirectional"))
      (node (ref "X5") (pin "4") (pinfunction "4_4") (pintype "bidirectional"))
      (node (ref "X5") (pin "5") (pinfunction "5_5") (pintype "bidirectional"))
    )
    (net (code "37") (name "Net-(D2-MCLR)") (class "Default")
      (node (ref "D2") (pin "1") (pinfunction "MCLR_1") (pintype "bidirectional"))
      (node (ref "JP1") (pin "P$2") (pinfunction "P$2_P$2") (pintype "bidirectional"))
      (node (ref "R102") (pin "P$2") (pinfunction "2_P$2") (pintype "passive"))
    )
    (net (code "38") (name "Net-(D2-OSC1)") (class "Default")
      (node (ref "C112") (pin "1") (pinfunction "1_1") (pintype "passive"))
      (node (ref "D2") (pin "9") (pinfunction "OSC1_9") (pintype "bidirectional"))
      (node (ref "X2") (pin "1") (pinfunction "1_1") (pintype "passive"))
    )
    (net (code "39") (name "Net-(D2-OSC2)") (class "Default")
      (node (ref "C111") (pin "2") (pinfunction "2_2") (pintype "passive"))
      (node (ref "D2") (pin "10") (pinfunction "OSC2_10") (pintype "bidirectional"))
      (node (ref "X2") (pin "2") (pinfunction "2_2") (pintype "passive"))
    )
    (net (code "40") (name "Net-(D3-RST)") (class "Default")
      (node (ref "D3") (pin "1") (pinfunction "RST_1") (pintype "output"))
      (node (ref "JP1") (pin "P$3") (pinfunction "P$3_P$3") (pintype "bidirectional"))
    )
    (net (code "41") (name "Net-(DA1-CNT)") (class "Default")
      (node (ref "DA1") (pin "1") (pinfunction "CNT_1") (pintype "bidirectional"))
      (node (ref "R5") (pin "P$1") (pinfunction "1_P$1") (pintype "passive"))
    )
    (net (code "42") (name "Net-(DA1-NBP)") (class "Default")
      (node (ref "C12") (pin "1") (pinfunction "1_1") (pintype "passive"))
      (node (ref "DA1") (pin "3") (pinfunction "NBP_3") (pintype "bidirectional"))
    )
    (net (code "43") (name "Net-(DA3-+IN)") (class "Default")
      (node (ref "C8") (pin "1") (pinfunction "1_1") (pintype "passive"))
      (node (ref "DA3") (pin "3") (pinfunction "+IN_3") (pintype "input"))
      (node (ref "R4") (pin "P$2") (pinfunction "2_P$2") (pintype "passive"))
    )
    (net (code "44") (name "Net-(DA3--IN)") (class "Default")
      (node (ref "C15") (pin "1") (pinfunction "1_1") (pintype "passive"))
      (node (ref "DA3") (pin "2") (pinfunction "-IN_2") (pintype "input"))
      (node (ref "R10") (pin "P$2") (pinfunction "2_P$2") (pintype "passive"))
    )
    (net (code "45") (name "Net-(DA3-OUT)") (class "Default")
      (node (ref "C15") (pin "2") (pinfunction "2_2") (pintype "passive"))
      (node (ref "DA3") (pin "6") (pinfunction "OUT_6") (pintype "output"))
      (node (ref "R6") (pin "1") (pinfunction "1_1") (pintype "passive"))
    )
    (net (code "46") (name "Net-(FU1-1)") (class "Default")
      (node (ref "+6V") (pin "P$1") (pinfunction "P$1_P$1") (pintype "passive"))
      (node (ref "FU1") (pin "P$1") (pinfunction "1_P$1") (pintype "passive"))
    )
    (net (code "47") (name "Net-(IC2-+IN)") (class "Default")
      (node (ref "C13") (pin "1") (pinfunction "1_1") (pintype "passive"))
      (node (ref "IC2") (pin "3") (pinfunction "+IN_3") (pintype "input"))
      (node (ref "R100") (pin "P$2") (pinfunction "2_P$2") (pintype "passive"))
    )
    (net (code "48") (name "Net-(IC2--IN)") (class "Default")
      (node (ref "C14") (pin "1") (pinfunction "1_1") (pintype "passive"))
      (node (ref "IC2") (pin "2") (pinfunction "-IN_2") (pintype "input"))
      (node (ref "R8") (pin "P$2") (pinfunction "2_P$2") (pintype "passive"))
    )
    (net (code "49") (name "Net-(IC2-OUT)") (class "Default")
      (node (ref "C14") (pin "2") (pinfunction "2_2") (pintype "passive"))
      (node (ref "IC2") (pin "6") (pinfunction "OUT_6") (pintype "output"))
      (node (ref "R7") (pin "P$1") (pinfunction "1_P$1") (pintype "passive"))
    )
    (net (code "50") (name "Net-(IC3-+IN)") (class "Default")
      (node (ref "IC3") (pin "3") (pinfunction "+IN_3") (pintype "input"))
      (node (ref "R14") (pin "2") (pinfunction "2_2") (pintype "passive"))
      (node (ref "T2") (pin "3") (pinfunction "E_3") (pintype "passive"))
    )
    (net (code "51") (name "Net-(IC3--IN)") (class "Default")
      (node (ref "IC3") (pin "2") (pinfunction "-IN_2") (pintype "input"))
      (node (ref "R14") (pin "1") (pinfunction "1_1") (pintype "passive"))
      (node (ref "R24") (pin "1") (pinfunction "1_1") (pintype "passive"))
    )
    (net (code "52") (name "Net-(IC3-OUT)") (class "Default")
      (node (ref "IC3") (pin "6") (pinfunction "OUT_6") (pintype "output"))
      (node (ref "R11") (pin "P$2") (pinfunction "2_P$2") (pintype "passive"))
      (node (ref "R8") (pin "P$1") (pinfunction "1_P$1") (pintype "passive"))
    )
    (net (code "53") (name "Net-(IC4-+IN)") (class "Default")
      (node (ref "IC4") (pin "3") (pinfunction "+IN_3") (pintype "input"))
      (node (ref "R12") (pin "2") (pinfunction "2_2") (pintype "passive"))
      (node (ref "T1") (pin "3") (pinfunction "E_3") (pintype "passive"))
    )
    (net (code "54") (name "Net-(IC4--IN)") (class "Default")
      (node (ref "IC4") (pin "2") (pinfunction "-IN_2") (pintype "input"))
      (node (ref "R12") (pin "1") (pinfunction "1_1") (pintype "passive"))
      (node (ref "R25") (pin "1") (pinfunction "1_1") (pintype "passive"))
    )
    (net (code "55") (name "Net-(IC4-OUT)") (class "Default")
      (node (ref "IC4") (pin "6") (pinfunction "OUT_6") (pintype "output"))
      (node (ref "R10") (pin "P$1") (pinfunction "1_P$1") (pintype "passive"))
      (node (ref "R9") (pin "P$2") (pinfunction "2_P$2") (pintype "passive"))
    )
    (net (code "56") (name "Net-(IC5-+IN)") (class "Default")
      (node (ref "C23") (pin "2") (pinfunction "2_2") (pintype "passive"))
      (node (ref "C25") (pin "1") (pinfunction "1_1") (pintype "passive"))
      (node (ref "IC5") (pin "3") (pinfunction "+IN_3") (pintype "input"))
      (node (ref "R29") (pin "P$2") (pinfunction "2_P$2") (pintype "passive"))
    )
    (net (code "57") (name "Net-(IC5--IN)") (class "Default")
      (node (ref "C20") (pin "2") (pinfunction "2_2") (pintype "passive"))
      (node (ref "C23") (pin "1") (pinfunction "1_1") (pintype "passive"))
      (node (ref "IC5") (pin "2") (pinfunction "-IN_2") (pintype "input"))
      (node (ref "R28") (pin "P$2") (pinfunction "2_P$2") (pintype "passive"))
    )
    (net (code "58") (name "Net-(IC5-OUT)") (class "Default")
      (node (ref "IC5") (pin "6") (pinfunction "OUT_6") (pintype "output"))
      (node (ref "R19") (pin "P$1") (pinfunction "1_P$1") (pintype "passive"))
    )
    (net (code "59") (name "Net-(IC6-+IN)") (class "Default")
      (node (ref "C22") (pin "1") (pinfunction "1_1") (pintype "passive"))
      (node (ref "C24") (pin "2") (pinfunction "2_2") (pintype "passive"))
      (node (ref "IC6") (pin "3") (pinfunction "+IN_3") (pintype "input"))
      (node (ref "R26") (pin "P$2") (pinfunction "2_P$2") (pintype "passive"))
    )
    (net (code "60") (name "Net-(IC6--IN)") (class "Default")
      (node (ref "C21") (pin "2") (pinfunction "2_2") (pintype "passive"))
      (node (ref "C24") (pin "1") (pinfunction "1_1") (pintype "passive"))
      (node (ref "IC6") (pin "2") (pinfunction "-IN_2") (pintype "input"))
      (node (ref "R27") (pin "P$2") (pinfunction "2_P$2") (pintype "passive"))
    )
    (net (code "61") (name "Net-(IC6-OUT)") (class "Default")
      (node (ref "IC6") (pin "6") (pinfunction "OUT_6") (pintype "output"))
      (node (ref "R18") (pin "P$1") (pinfunction "1_P$1") (pintype "passive"))
    )
    (net (code "62") (name "Net-(K1A-2)") (class "Default")
      (node (ref "D1") (pin "A") (pinfunction "A_A") (pintype "passive"))
      (node (ref "K1") (pin "16") (pinfunction "2_16") (pintype "passive"))
      (node (ref "VT1") (pin "2") (pinfunction "C_2") (pintype "passive"))
    )
    (net (code "63") (name "Net-(K1B-O)") (class "Default")
      (node (ref "K1") (pin "O1") (pinfunction "O_O1") (pintype "passive"))
      (node (ref "P2") (pin "P$1") (pinfunction "P$1_P$1") (pintype "passive"))
    )
    (net (code "64") (name "Net-(K1B-P)") (class "Default")
      (node (ref "K1") (pin "P1") (pinfunction "P_P1") (pintype "passive"))
      (node (ref "P3") (pin "P$1") (pinfunction "P$1_P$1") (pintype "passive"))
    )
    (net (code "65") (name "Net-(K1B-S)") (class "Default")
      (node (ref "K1") (pin "S1") (pinfunction "S_S1") (pintype "passive"))
      (node (ref "P1") (pin "P$1") (pinfunction "P$1_P$1") (pintype "passive"))
    )
    (net (code "66") (name "Net-(K1C-O)") (class "Default")
      (node (ref "K1") (pin "O2") (pinfunction "O_O2") (pintype "passive"))
      (node (ref "P5") (pin "P$1") (pinfunction "P$1_P$1") (pintype "passive"))
    )
    (net (code "67") (name "Net-(K1C-P)") (class "Default")
      (node (ref "K1") (pin "P2") (pinfunction "P_P2") (pintype "passive"))
      (node (ref "P6") (pin "P$1") (pinfunction "P$1_P$1") (pintype "passive"))
    )
    (net (code "68") (name "Net-(K1C-S)") (class "Default")
      (node (ref "K1") (pin "S2") (pinfunction "S_S2") (pintype "passive"))
      (node (ref "P4") (pin "P$1") (pinfunction "P$1_P$1") (pintype "passive"))
    )
    (net (code "69") (name "Net-(R7-2)") (class "Default")
      (node (ref "R7") (pin "P$2") (pinfunction "2_P$2") (pintype "passive"))
      (node (ref "T2") (pin "1") (pinfunction "B_1") (pintype "passive"))
    )
    (net (code "70") (name "Net-(R13-1)") (class "Default")
      (node (ref "R13") (pin "P$1") (pinfunction "1_P$1") (pintype "passive"))
      (node (ref "R16") (pin "P$1") (pinfunction "1_P$1") (pintype "passive"))
    )
    (net (code "71") (name "Net-(R13-2)") (class "Default")
      (node (ref "IC3") (pin "8") (pinfunction "RG_8") (pintype "passive"))
      (node (ref "R13") (pin "P$2") (pinfunction "2_P$2") (pintype "passive"))
    )
    (net (code "72") (name "Net-(R15-1)") (class "Default")
      (node (ref "IC4") (pin "8") (pinfunction "RG_8") (pintype "passive"))
      (node (ref "R15") (pin "P$1") (pinfunction "1_P$1") (pintype "passive"))
    )
    (net (code "73") (name "Net-(R15-2)") (class "Default")
      (node (ref "R15") (pin "P$2") (pinfunction "2_P$2") (pintype "passive"))
      (node (ref "R17") (pin "P$2") (pinfunction "2_P$2") (pintype "passive"))
    )
    (net (code "74") (name "Net-(R16-2)") (class "Default")
      (node (ref "IC3") (pin "1") (pinfunction "RG_1") (pintype "passive"))
      (node (ref "R16") (pin "P$2") (pinfunction "2_P$2") (pintype "passive"))
    )
    (net (code "75") (name "Net-(R17-1)") (class "Default")
      (node (ref "IC4") (pin "1") (pinfunction "RG_1") (pintype "passive"))
      (node (ref "R17") (pin "P$1") (pinfunction "1_P$1") (pintype "passive"))
    )
    (net (code "76") (name "Net-(R20-1)") (class "Default")
      (node (ref "IC5") (pin "8") (pinfunction "RG_8") (pintype "passive"))
      (node (ref "R20") (pin "P$1") (pinfunction "1_P$1") (pintype "passive"))
    )
    (net (code "77") (name "Net-(R20-2)") (class "Default")
      (node (ref "R20") (pin "P$2") (pinfunction "2_P$2") (pintype "passive"))
      (node (ref "R22") (pin "P$2") (pinfunction "2_P$2") (pintype "passive"))
    )
    (net (code "78") (name "Net-(R21-1)") (class "Default")
      (node (ref "IC6") (pin "8") (pinfunction "RG_8") (pintype "passive"))
      (node (ref "R21") (pin "P$1") (pinfunction "1_P$1") (pintype "passive"))
    )
    (net (code "79") (name "Net-(R21-2)") (class "Default")
      (node (ref "R21") (pin "P$2") (pinfunction "2_P$2") (pintype "passive"))
      (node (ref "R23") (pin "P$2") (pinfunction "2_P$2") (pintype "passive"))
    )
    (net (code "80") (name "Net-(R22-1)") (class "Default")
      (node (ref "IC5") (pin "1") (pinfunction "RG_1") (pintype "passive"))
      (node (ref "R22") (pin "P$1") (pinfunction "1_P$1") (pintype "passive"))
    )
    (net (code "81") (name "Net-(R23-1)") (class "Default")
      (node (ref "IC6") (pin "1") (pinfunction "RG_1") (pintype "passive"))
      (node (ref "R23") (pin "P$1") (pinfunction "1_P$1") (pintype "passive"))
    )
    (net (code "82") (name "Net-(RP2-P$5)") (class "Default")
      (node (ref "RP2") (pin "5") (pinfunction "P$5_5") (pintype "passive"))
      (node (ref "VD4") (pin "C") (pinfunction "C_C") (pintype "passive"))
    )
    (net (code "83") (name "Net-(T1-B)") (class "Default")
      (node (ref "R6") (pin "2") (pinfunction "2_2") (pintype "passive"))
      (node (ref "T1") (pin "1") (pinfunction "B_1") (pintype "passive"))
    )
    (net (code "84") (name "Net-(VT1-B)") (class "Default")
      (node (ref "R3") (pin "1") (pinfunction "1_1") (pintype "passive"))
      (node (ref "VT1") (pin "3") (pinfunction "B_3") (pintype "passive"))
    )
    (net (code "85") (name "Net-(WINSTAR_DISP1-AVEE)") (class "Default")
      (node (ref "R2") (pin "2") (pinfunction "2_2") (pintype "passive"))
      (node (ref "WINSTAR_DISP1") (pin "P$11") (pinfunction "AVEE_P$11") (pintype "bidirectional"))
    )
    (net (code "86") (name "Net-(WINSTAR_DISP1-V0CON)") (class "Default")
      (node (ref "R1") (pin "3") (pinfunction "3_3") (pintype "passive"))
      (node (ref "WINSTAR_DISP1") (pin "P$3") (pinfunction "V0CON_P$3") (pintype "bidirectional"))
    )
    (net (code "87") (name "unconnected-(D2-RC0{slash}T1CKI-Pad11)") (class "Default")
      (node (ref "D2") (pin "11") (pinfunction "RC0/T1CKI_11") (pintype "bidirectional"))
    )
  )
)
